# S7CAS-PLEIADES-CARTE-MERE_P20_USB.net
KiCad netlist of a schematic drawn in Altium Designer
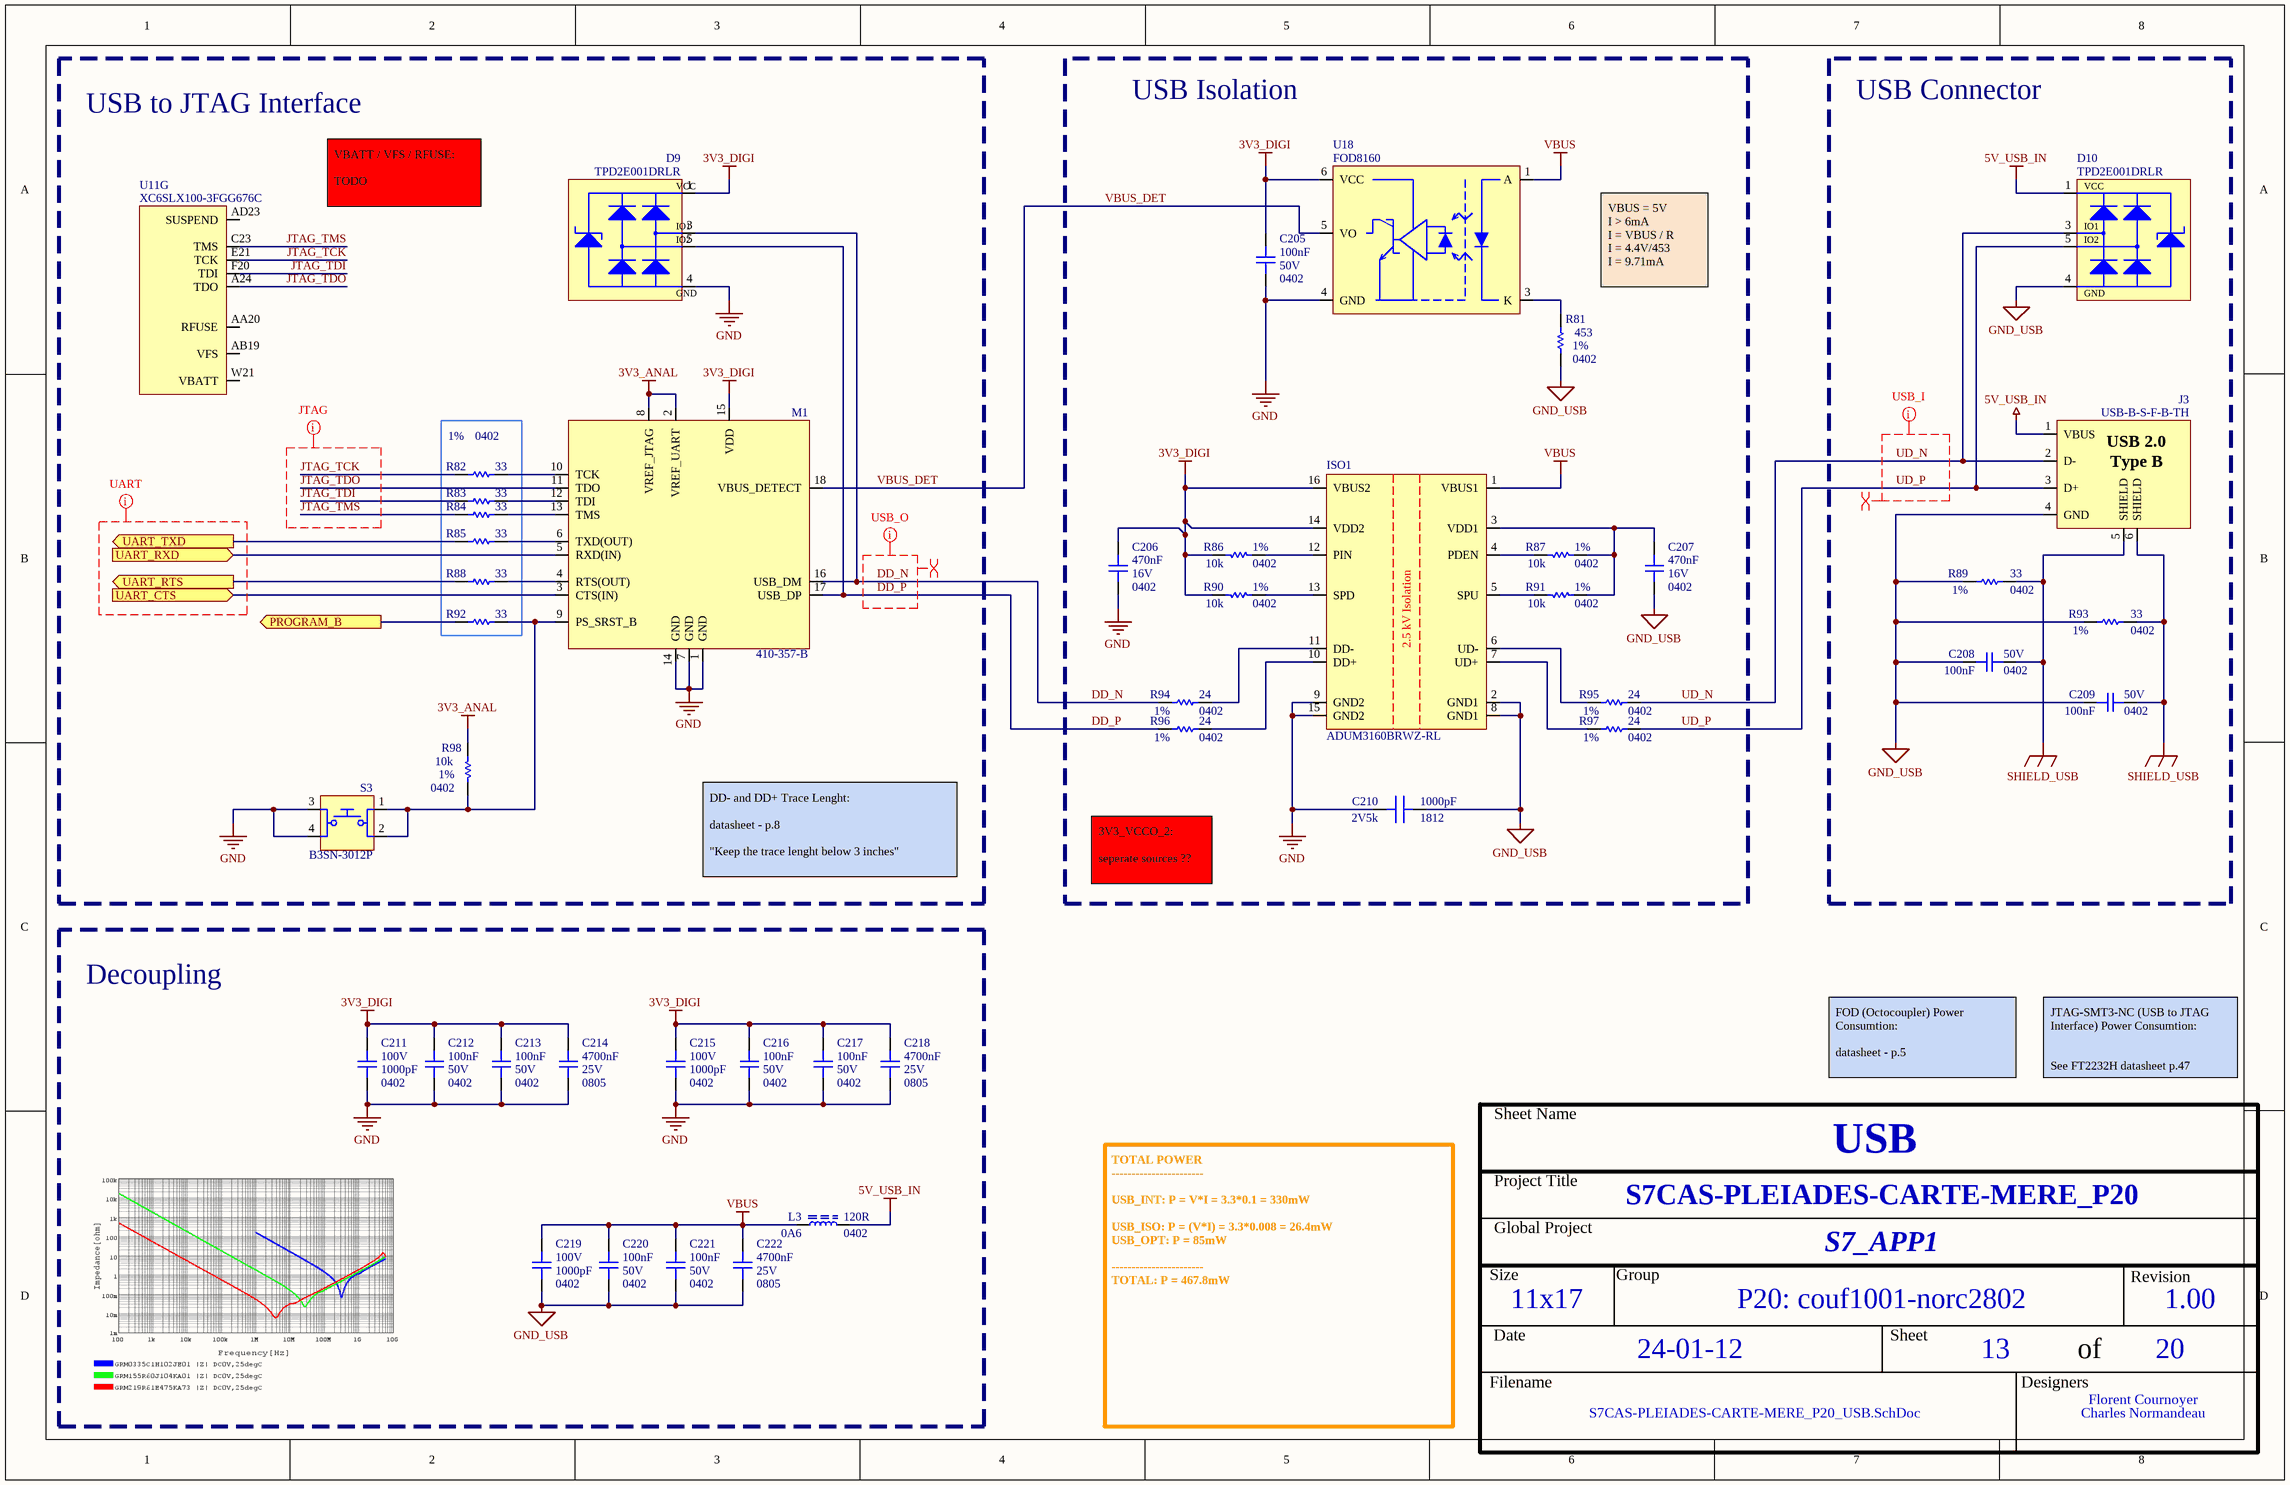
[diagram p0: S7CAS-PLEIADES-CARTE-MERE_P20_USB.SchDoc]

(export (version "E")
  (design (tool "Eeschema 10.0.6"))
  (components
    (comp (ref "C205")
      (value "100nF")
      (footprint "CAP_0402")
      (description "CAP - 0402")
      (fields
        (field (name "MFG PART NUMBER") "GRM155R61H104KE14")
        (field (name "VOLTAGE") "50V")
        (field (name "PACKAGE") "0402")
        (field (name "CREATEDBY") "Jonathan Bouchard")
      )
      (libsource (lib "S7CAS_LIB2023") (part "CAP - 0402"))
    )
    (comp (ref "C206")
      (value "470nF")
      (footprint "CAP_0402")
      (description "CAP - 0402")
      (fields
        (field (name "MFG PART NUMBER") "GXT155R61C474KE01")
        (field (name "VOLTAGE") "16V")
        (field (name "PACKAGE") "0402")
        (field (name "CREATEDBY") "Jonathan Bouchard")
      )
      (libsource (lib "S7CAS_LIB2023") (part "CAP - 0402"))
    )
    (comp (ref "C207")
      (value "470nF")
      (footprint "CAP_0402")
      (description "CAP - 0402")
      (fields
        (field (name "MFG PART NUMBER") "GXT155R61C474KE01")
        (field (name "VOLTAGE") "16V")
        (field (name "PACKAGE") "0402")
        (field (name "CREATEDBY") "Jonathan Bouchard")
      )
      (libsource (lib "S7CAS_LIB2023") (part "CAP - 0402"))
    )
    (comp (ref "C208")
      (value "100nF")
      (footprint "CAP_0402")
      (description "CAP - 0402")
      (fields
        (field (name "MFG PART NUMBER") "GRM155R61H104KE14")
        (field (name "VOLTAGE") "50V")
        (field (name "PACKAGE") "0402")
        (field (name "CREATEDBY") "Jonathan Bouchard")
      )
      (libsource (lib "S7CAS_LIB2023") (part "CAP - 0402"))
    )
    (comp (ref "C209")
      (value "100nF")
      (footprint "CAP_0402")
      (description "CAP - 0402")
      (fields
        (field (name "MFG PART NUMBER") "GRM155R61H104KE14")
        (field (name "VOLTAGE") "50V")
        (field (name "PACKAGE") "0402")
        (field (name "CREATEDBY") "Jonathan Bouchard")
      )
      (libsource (lib "S7CAS_LIB2023") (part "CAP - 0402"))
    )
    (comp (ref "C210")
      (value "1000pF")
      (footprint "CAP_CER_1812")
      (description "CAP - CER 1000PF 2.5KV X7R - 1812")
      (fields
        (field (name "TOLERANCE") "10%")
        (field (name "PACKAGE") "1812")
        (field (name "VOLTAGE RATING") "2V5k")
        (field (name "Comment") "1812WC102KAT1A")
      )
      (libsource (lib "LIB_TEMP_P20_FLORENT_COURNOYER_SCH") (part "CAP_CER_1812WC102KAT1A"))
    )
    (comp (ref "C211")
      (value "1000pF")
      (footprint "CAP_0402")
      (description "CAP - 0402")
      (fields
        (field (name "MFG PART NUMBER") "GRM155R72A102KA01")
        (field (name "VOLTAGE") "100V")
        (field (name "PACKAGE") "0402")
        (field (name "CREATEDBY") "Jonathan Bouchard")
      )
      (libsource (lib "S7CAS_LIB2023") (part "CAP - 0402"))
    )
    (comp (ref "C212")
      (value "100nF")
      (footprint "CAP_0402")
      (description "CAP - 0402")
      (fields
        (field (name "MFG PART NUMBER") "GRM155R61H104KE14")
        (field (name "VOLTAGE") "50V")
        (field (name "PACKAGE") "0402")
        (field (name "CREATEDBY") "Jonathan Bouchard")
      )
      (libsource (lib "S7CAS_LIB2023") (part "CAP - 0402"))
    )
    (comp (ref "C213")
      (value "100nF")
      (footprint "CAP_0402")
      (description "CAP - 0402")
      (fields
        (field (name "MFG PART NUMBER") "GRM155R61H104KE14")
        (field (name "VOLTAGE") "50V")
        (field (name "PACKAGE") "0402")
        (field (name "CREATEDBY") "Jonathan Bouchard")
      )
      (libsource (lib "S7CAS_LIB2023") (part "CAP - 0402"))
    )
    (comp (ref "C214")
      (value "4700nF")
      (footprint "CAP_0805")
      (description "CAP - 0805")
      (fields
        (field (name "MFG PART NUMBER") "GRM219R61E475KA73")
        (field (name "VOLTAGE") "25V")
        (field (name "PACKAGE") "0805")
        (field (name "CREATEDBY") "Jonathan Bouchard")
      )
      (libsource (lib "S7CAS_LIB2023") (part "CAP - 0805"))
    )
    (comp (ref "C215")
      (value "1000pF")
      (footprint "CAP_0402")
      (description "CAP - 0402")
      (fields
        (field (name "MFG PART NUMBER") "GRM155R72A102KA01")
        (field (name "VOLTAGE") "100V")
        (field (name "PACKAGE") "0402")
        (field (name "CREATEDBY") "Jonathan Bouchard")
      )
      (libsource (lib "S7CAS_LIB2023") (part "CAP - 0402"))
    )
    (comp (ref "C216")
      (value "100nF")
      (footprint "CAP_0402")
      (description "CAP - 0402")
      (fields
        (field (name "MFG PART NUMBER") "GRM155R61H104KE14")
        (field (name "VOLTAGE") "50V")
        (field (name "PACKAGE") "0402")
        (field (name "CREATEDBY") "Jonathan Bouchard")
      )
      (libsource (lib "S7CAS_LIB2023") (part "CAP - 0402"))
    )
    (comp (ref "C217")
      (value "100nF")
      (footprint "CAP_0402")
      (description "CAP - 0402")
      (fields
        (field (name "MFG PART NUMBER") "GRM155R61H104KE14")
        (field (name "VOLTAGE") "50V")
        (field (name "PACKAGE") "0402")
        (field (name "CREATEDBY") "Jonathan Bouchard")
      )
      (libsource (lib "S7CAS_LIB2023") (part "CAP - 0402"))
    )
    (comp (ref "C218")
      (value "4700nF")
      (footprint "CAP_0805")
      (description "CAP - 0805")
      (fields
        (field (name "MFG PART NUMBER") "GRM219R61E475KA73")
        (field (name "VOLTAGE") "25V")
        (field (name "PACKAGE") "0805")
        (field (name "CREATEDBY") "Jonathan Bouchard")
      )
      (libsource (lib "S7CAS_LIB2023") (part "CAP - 0805"))
    )
    (comp (ref "C219")
      (value "1000pF")
      (footprint "CAP_0402")
      (description "CAP - 0402")
      (fields
        (field (name "MFG PART NUMBER") "GRM155R72A102KA01")
        (field (name "VOLTAGE") "100V")
        (field (name "PACKAGE") "0402")
        (field (name "CREATEDBY") "Jonathan Bouchard")
      )
      (libsource (lib "S7CAS_LIB2023") (part "CAP - 0402"))
    )
    (comp (ref "C220")
      (value "100nF")
      (footprint "CAP_0402")
      (description "CAP - 0402")
      (fields
        (field (name "MFG PART NUMBER") "GRM155R61H104KE14")
        (field (name "VOLTAGE") "50V")
        (field (name "PACKAGE") "0402")
        (field (name "CREATEDBY") "Jonathan Bouchard")
      )
      (libsource (lib "S7CAS_LIB2023") (part "CAP - 0402"))
    )
    (comp (ref "C221")
      (value "100nF")
      (footprint "CAP_0402")
      (description "CAP - 0402")
      (fields
        (field (name "MFG PART NUMBER") "GRM155R61H104KE14")
        (field (name "VOLTAGE") "50V")
        (field (name "PACKAGE") "0402")
        (field (name "CREATEDBY") "Jonathan Bouchard")
      )
      (libsource (lib "S7CAS_LIB2023") (part "CAP - 0402"))
    )
    (comp (ref "C222")
      (value "4700nF")
      (footprint "CAP_0805")
      (description "CAP - 0805")
      (fields
        (field (name "MFG PART NUMBER") "GRM219R61E475KA73")
        (field (name "VOLTAGE") "25V")
        (field (name "PACKAGE") "0805")
        (field (name "CREATEDBY") "Jonathan Bouchard")
      )
      (libsource (lib "S7CAS_LIB2023") (part "CAP - 0805"))
    )
    (comp (ref "D9")
      (value "TPD2E001DRLR")
      (footprint "TVS_USB_TPD2E001DRLR")
      (description "TVS - USB TVS DIODE 5.5V - SOT-553")
      (fields
        (field (name "CREATEDBY/DATE") "Jonathan Bouchard 2018-07-10")
        (field (name "VERIFIEDBY") "Arnaud Samson 16-07-18")
      )
      (libsource (lib "") (part "TVS_USB_TPD2E001DRLR_1"))
    )
    (comp (ref "D10")
      (value "TPD2E001DRLR")
      (footprint "TVS_USB_TPD2E001DRLR")
      (description "TVS - USB TVS DIODE 5.5V - SOT-553")
      (fields
        (field (name "CREATEDBY/DATE") "Jonathan Bouchard 2018-07-10")
        (field (name "VERIFIEDBY") "Arnaud Samson 16-07-18")
      )
      (libsource (lib "S7CAS_LIB2023") (part "TVS_USB_TPD2E001DRLR"))
    )
    (comp (ref "ISO1")
      (value "ADUM3160BRWZ-RL")
      (footprint "ISO_ADUM3160BRWZ-RL")
      (description "ISO - DGTL ISO 2.5KV 2CH USB - 16SOIC")
      (fields
        (field (name "CREATEDBY/DATE") "Tommy Rossignol 2018-11-16")
        (field (name "VERIFIEDBY") "Caroline Paulin - 13 février 2019")
      )
      (libsource (lib "S7CAS_LIB2023") (part "ISO_ADUM3160BRWZ-RL"))
    )
    (comp (ref "J3")
      (value "USB-B-S-F-B-TH")
      (footprint "CON_USB_USB-B-S-F-B-TH")
      (description "CON - USB B RECPT TH R/A - 4-TH")
      (fields
        (field (name "MFG PART NUMBER") "CON_USB_USB-B-S-F-B-TH")
        (field (name "CREATEDBY/DATE") "Jonathan Bouchard 2020-03-24")
        (field (name "VERIFIEDBY") "C.Paulin - 22/04/2020")
      )
      (libsource (lib "S7CAS_LIB2023") (part "CON_USB_USB-B-S-F-B-TH"))
    )
    (comp (ref "L3")
      (value "120R")
      (footprint "FER_0402")
      (description "FER - 0402")
      (fields
        (field (name "MFG PART NUMBER") "BLM15BX121SN1")
        (field (name "CURRENT") "0A6")
        (field (name "PACKAGE") "0402")
        (field (name "CREATEDBY") "Jonathan Bouchard")
      )
      (libsource (lib "S7CAS_LIB2023") (part "FER - 0402"))
    )
    (comp (ref "M1")
      (value "410-357-B")
      (footprint "MOD_JTAG_410-357-B")
      (description "MOD - JTAG-SMT3-NC Programming Module For Xilinx FPGA - 18-SMT")
      (fields
        (field (name "CREATEDBY/DATE") "Tommy Rossignol 2018-11-23")
        (field (name "VERIFIEDBY") "Nicolas V. (2019-01-28)")
      )
      (libsource (lib "S7CAS_LIB2023") (part "MOD_JTAG_410-357-B"))
    )
    (comp (ref "R81")
      (value "453")
      (footprint "RES_0402")
      (description "RES - 0402")
      (fields
        (field (name "VOLTAGE") "50V")
        (field (name "MFG PART NUMBER") "RGC1/16SC6980FTH")
        (field (name "PACKAGE") "0402")
        (field (name "PRECISION") "1%")
        (field (name "CREATEDBY") "Jonathan Bouchard")
      )
      (libsource (lib "S7CAS_LIB2023") (part "RES - 0402"))
    )
    (comp (ref "R82")
      (value "33")
      (footprint "RES_0402")
      (description "RES - 0402")
      (fields
        (field (name "VOLTAGE") "50V")
        (field (name "POWER") "1/16W")
        (field (name "PACKAGE") "0402")
        (field (name "PRECISION") "1%")
        (field (name "CREATEDBY") "Jonathan Bouchard")
      )
      (libsource (lib "S7CAS_LIB2023") (part "RES - 0402"))
    )
    (comp (ref "R83")
      (value "33")
      (footprint "RES_0402")
      (description "RES - 0402")
      (fields
        (field (name "VOLTAGE") "50V")
        (field (name "POWER") "1/16W")
        (field (name "CREATEDBY") "Jonathan Bouchard")
      )
      (libsource (lib "S7CAS_LIB2023") (part "RES - 0402"))
    )
    (comp (ref "R84")
      (value "33")
      (footprint "RES_0402")
      (description "RES - 0402")
      (fields
        (field (name "VOLTAGE") "50V")
        (field (name "POWER") "1/16W")
        (field (name "CREATEDBY") "Jonathan Bouchard")
      )
      (libsource (lib "S7CAS_LIB2023") (part "RES - 0402"))
    )
    (comp (ref "R85")
      (value "33")
      (footprint "RES_0402")
      (description "RES - 0402")
      (fields
        (field (name "VOLTAGE") "50V")
        (field (name "POWER") "1/16W")
        (field (name "CREATEDBY") "Jonathan Bouchard")
      )
      (libsource (lib "S7CAS_LIB2023") (part "RES - 0402"))
    )
    (comp (ref "R86")
      (value "10k")
      (footprint "RES_0402")
      (description "RES - 0402")
      (fields
        (field (name "VOLTAGE") "50V")
        (field (name "MFG PART NUMBER") "MCS04020C1002FE000")
        (field (name "PACKAGE") "0402")
        (field (name "PRECISION") "1%")
        (field (name "CREATEDBY") "Jonathan Bouchard")
      )
      (libsource (lib "S7CAS_LIB2023") (part "RES - 0402"))
    )
    (comp (ref "R87")
      (value "10k")
      (footprint "RES_0402")
      (description "RES - 0402")
      (fields
        (field (name "VOLTAGE") "50V")
        (field (name "MFG PART NUMBER") "MCS04020C1002FE000")
        (field (name "PACKAGE") "0402")
        (field (name "PRECISION") "1%")
        (field (name "CREATEDBY") "Jonathan Bouchard")
      )
      (libsource (lib "S7CAS_LIB2023") (part "RES - 0402"))
    )
    (comp (ref "R88")
      (value "33")
      (footprint "RES_0402")
      (description "RES - 0402")
      (fields
        (field (name "VOLTAGE") "50V")
        (field (name "POWER") "1/16W")
        (field (name "CREATEDBY") "Jonathan Bouchard")
      )
      (libsource (lib "S7CAS_LIB2023") (part "RES - 0402"))
    )
    (comp (ref "R89")
      (value "33")
      (footprint "RES_0402")
      (description "RES - 0402")
      (fields
        (field (name "VOLTAGE") "50V")
        (field (name "POWER") "1/16W")
        (field (name "PACKAGE") "0402")
        (field (name "PRECISION") "1%")
        (field (name "CREATEDBY") "Jonathan Bouchard")
      )
      (libsource (lib "S7CAS_LIB2023") (part "RES - 0402"))
    )
    (comp (ref "R90")
      (value "10k")
      (footprint "RES_0402")
      (description "RES - 0402")
      (fields
        (field (name "VOLTAGE") "50V")
        (field (name "MFG PART NUMBER") "MCS04020C1002FE000")
        (field (name "PACKAGE") "0402")
        (field (name "PRECISION") "1%")
        (field (name "CREATEDBY") "Jonathan Bouchard")
      )
      (libsource (lib "S7CAS_LIB2023") (part "RES - 0402"))
    )
    (comp (ref "R91")
      (value "10k")
      (footprint "RES_0402")
      (description "RES - 0402")
      (fields
        (field (name "VOLTAGE") "50V")
        (field (name "MFG PART NUMBER") "MCS04020C1002FE000")
        (field (name "PACKAGE") "0402")
        (field (name "PRECISION") "1%")
        (field (name "CREATEDBY") "Jonathan Bouchard")
      )
      (libsource (lib "S7CAS_LIB2023") (part "RES - 0402"))
    )
    (comp (ref "R92")
      (value "33")
      (footprint "RES_0402")
      (description "RES - 0402")
      (fields
        (field (name "VOLTAGE") "50V")
        (field (name "POWER") "1/16W")
        (field (name "CREATEDBY") "Jonathan Bouchard")
      )
      (libsource (lib "S7CAS_LIB2023") (part "RES - 0402"))
    )
    (comp (ref "R93")
      (value "33")
      (footprint "RES_0402")
      (description "RES - 0402")
      (fields
        (field (name "VOLTAGE") "50V")
        (field (name "POWER") "1/16W")
        (field (name "PACKAGE") "0402")
        (field (name "PRECISION") "1%")
        (field (name "CREATEDBY") "Jonathan Bouchard")
      )
      (libsource (lib "S7CAS_LIB2023") (part "RES - 0402"))
    )
    (comp (ref "R94")
      (value "24")
      (footprint "RES_0402")
      (description "RES - 0402")
      (fields
        (field (name "VOLTAGE") "50V")
        (field (name "MFG PART NUMBER") "MCS04020C2409FE000")
        (field (name "PACKAGE") "0402")
        (field (name "PRECISION") "1%")
        (field (name "CREATEDBY") "Jonathan Bouchard")
      )
      (libsource (lib "S7CAS_LIB2023") (part "RES - 0402"))
    )
    (comp (ref "R95")
      (value "24")
      (footprint "RES_0402")
      (description "RES - 0402")
      (fields
        (field (name "VOLTAGE") "50V")
        (field (name "MFG PART NUMBER") "MCS04020C2409FE000")
        (field (name "PACKAGE") "0402")
        (field (name "PRECISION") "1%")
        (field (name "CREATEDBY") "Jonathan Bouchard")
      )
      (libsource (lib "S7CAS_LIB2023") (part "RES - 0402"))
    )
    (comp (ref "R96")
      (value "24")
      (footprint "RES_0402")
      (description "RES - 0402")
      (fields
        (field (name "VOLTAGE") "50V")
        (field (name "MFG PART NUMBER") "MCS04020C2409FE000")
        (field (name "PACKAGE") "0402")
        (field (name "PRECISION") "1%")
        (field (name "CREATEDBY") "Jonathan Bouchard")
      )
      (libsource (lib "S7CAS_LIB2023") (part "RES - 0402"))
    )
    (comp (ref "R97")
      (value "24")
      (footprint "RES_0402")
      (description "RES - 0402")
      (fields
        (field (name "VOLTAGE") "50V")
        (field (name "MFG PART NUMBER") "MCS04020C2409FE000")
        (field (name "PACKAGE") "0402")
        (field (name "PRECISION") "1%")
        (field (name "CREATEDBY") "Jonathan Bouchard")
      )
      (libsource (lib "S7CAS_LIB2023") (part "RES - 0402"))
    )
    (comp (ref "R98")
      (value "10k")
      (footprint "RES_0402")
      (description "RES - 0402")
      (fields
        (field (name "VOLTAGE") "50V")
        (field (name "MFG PART NUMBER") "MCS04020C1002FE000")
        (field (name "PACKAGE") "0402")
        (field (name "PRECISION") "1%")
        (field (name "CREATEDBY") "Jonathan Bouchard")
      )
      (libsource (lib "S7CAS_LIB2023") (part "RES - 0402"))
    )
    (comp (ref "S3")
      (value "B3SN-3012P")
      (footprint "SWI_TACT_B3SN-3012P")
      (description "SWI - SWITCH TACTILE SPST-NO 0.05A 24V -SMD")
      (fields
        (field (name "CREATEDBY/DATE") "Olivier Bernard / 5/12/2017")
        (field (name "VERIFIEDBY") "Caroline Paulin / 11 juillet 2018")
      )
      (libsource (lib "S7CAS_LIB2023") (part "SWI_TACT_B3SN-3012P_1"))
    )
    (comp (ref "U11")
      (value "XC6SLX100-3FGG676C")
      (footprint "FPGA_XILINX_FGG676")
      (description "FPGA - XILINX SPARTAN 6 480 I/O - BGA-676")
      (fields
        (field (name "VOLTAGE") "1.14 V ~ 1.26 V")
        (field (name "MFG") "Xilinx")
        (field (name "CREATEDBY") "Jonathan Bouchard")
      )
      (libsource (lib "S7CAS_LIB2023") (part "FPGA_XC6SLX100-3FGG676C"))
    )
    (comp (ref "U18")
      (value "FOD8160")
      (footprint "FOD8160")
      (description "XXX - Description - Package")
      (libsource (lib "LIB_TEMP_P20_FLORENT_COURNOYER_SCH") (part "OCTOCOUPLER_FOD8160"))
    )
  )
  (nets
    (net (code "1") (name "/DD_N") (class "Default")
      (node (ref "D9") (pin "3") (pinfunction "IO1_3") (pintype "passive"))
      (node (ref "M1") (pin "16") (pinfunction "USB_DM_16") (pintype "passive"))
      (node (ref "R94") (pin "2") (pinfunction "2_2") (pintype "passive"))
    )
    (net (code "2") (name "/DD_P") (class "Default")
      (node (ref "D9") (pin "5") (pinfunction "IO2_5") (pintype "passive"))
      (node (ref "M1") (pin "17") (pinfunction "USB_DP_17") (pintype "passive"))
      (node (ref "R96") (pin "2") (pinfunction "2_2") (pintype "passive"))
    )
    (net (code "3") (name "/JTAG_TCK") (class "Default")
      (node (ref "R82") (pin "2") (pinfunction "2_2") (pintype "passive"))
      (node (ref "U11") (pin "E21") (pinfunction "TCK_E21") (pintype "passive"))
    )
    (net (code "4") (name "/JTAG_TDI") (class "Default")
      (node (ref "R83") (pin "2") (pinfunction "2_2") (pintype "passive"))
      (node (ref "U11") (pin "F20") (pinfunction "TDI_F20") (pintype "passive"))
    )
    (net (code "5") (name "/JTAG_TDO") (class "Default")
      (node (ref "M1") (pin "11") (pinfunction "TDO_11") (pintype "passive"))
      (node (ref "U11") (pin "A24") (pinfunction "TDO_A24") (pintype "passive"))
    )
    (net (code "6") (name "/JTAG_TMS") (class "Default")
      (node (ref "R84") (pin "2") (pinfunction "2_2") (pintype "passive"))
      (node (ref "U11") (pin "C23") (pinfunction "TMS_C23") (pintype "passive"))
    )
    (net (code "7") (name "/PROGRAM_B") (class "Default")
      (node (ref "R92") (pin "2") (pinfunction "2_2") (pintype "passive"))
    )
    (net (code "8") (name "/UART_CTS") (class "Default")
      (node (ref "M1") (pin "3") (pinfunction "CTS(IN)_3") (pintype "passive"))
    )
    (net (code "9") (name "/UART_RTS") (class "Default")
      (node (ref "R88") (pin "2") (pinfunction "2_2") (pintype "passive"))
    )
    (net (code "10") (name "/UART_RXD") (class "Default")
      (node (ref "M1") (pin "5") (pinfunction "RXD(IN)_5") (pintype "passive"))
    )
    (net (code "11") (name "/UART_TXD") (class "Default")
      (node (ref "R85") (pin "2") (pinfunction "2_2") (pintype "passive"))
    )
    (net (code "12") (name "/UD_N") (class "Default")
      (node (ref "D10") (pin "3") (pinfunction "IO1_3") (pintype "passive"))
      (node (ref "J3") (pin "2") (pinfunction "D-_2") (pintype "passive"))
      (node (ref "R95") (pin "1") (pinfunction "1_1") (pintype "passive"))
    )
    (net (code "13") (name "/UD_P") (class "Default")
      (node (ref "D10") (pin "5") (pinfunction "IO2_5") (pintype "passive"))
      (node (ref "J3") (pin "3") (pinfunction "D+_3") (pintype "passive"))
      (node (ref "R97") (pin "1") (pinfunction "1_1") (pintype "passive"))
    )
    (net (code "14") (name "/VBUS_DET") (class "Default")
      (node (ref "M1") (pin "18") (pinfunction "VBUS_DETECT_18") (pintype "passive"))
      (node (ref "U18") (pin "5") (pinfunction "VO_5") (pintype "passive"))
    )
    (net (code "15") (name "3V3_ANAL") (class "Default")
      (node (ref "M1") (pin "2") (pinfunction "VREF_UART_2") (pintype "passive"))
      (node (ref "M1") (pin "8") (pinfunction "VREF_JTAG_8") (pintype "passive"))
      (node (ref "R98") (pin "2") (pinfunction "2_2") (pintype "passive"))
    )
    (net (code "16") (name "3V3_DIGI") (class "Default")
      (node (ref "C205") (pin "2") (pinfunction "2_2") (pintype "passive"))
      (node (ref "C206") (pin "2") (pinfunction "2_2") (pintype "passive"))
      (node (ref "C211") (pin "1") (pinfunction "1_1") (pintype "passive"))
      (node (ref "C212") (pin "2") (pinfunction "2_2") (pintype "passive"))
      (node (ref "C213") (pin "2") (pinfunction "2_2") (pintype "passive"))
      (node (ref "C214") (pin "2") (pinfunction "2_2") (pintype "passive"))
      (node (ref "C215") (pin "1") (pinfunction "1_1") (pintype "passive"))
      (node (ref "C216") (pin "2") (pinfunction "2_2") (pintype "passive"))
      (node (ref "C217") (pin "2") (pinfunction "2_2") (pintype "passive"))
      (node (ref "C218") (pin "2") (pinfunction "2_2") (pintype "passive"))
      (node (ref "D9") (pin "1") (pinfunction "VCC_1") (pintype "passive"))
      (node (ref "ISO1") (pin "14") (pinfunction "VDD2_14") (pintype "passive"))
      (node (ref "ISO1") (pin "16") (pinfunction "VBUS2_16") (pintype "passive"))
      (node (ref "M1") (pin "15") (pinfunction "VDD_15") (pintype "passive"))
      (node (ref "R86") (pin "2") (pinfunction "2_2") (pintype "passive"))
      (node (ref "R90") (pin "2") (pinfunction "2_2") (pintype "passive"))
      (node (ref "U18") (pin "6") (pinfunction "VCC_6") (pintype "passive"))
    )
    (net (code "17") (name "5V_USB_IN") (class "Default")
      (node (ref "D10") (pin "1") (pinfunction "VCC_1") (pintype "passive"))
      (node (ref "J3") (pin "1") (pinfunction "VBUS_1") (pintype "passive"))
      (node (ref "L3") (pin "1") (pinfunction "1_1") (pintype "passive"))
    )
    (net (code "18") (name "GND") (class "Default")
      (node (ref "C205") (pin "1") (pinfunction "1_1") (pintype "passive"))
      (node (ref "C206") (pin "1") (pinfunction "1_1") (pintype "passive"))
      (node (ref "C210") (pin "2") (pinfunction "2_2") (pintype "passive"))
      (node (ref "C211") (pin "2") (pinfunction "2_2") (pintype "passive"))
      (node (ref "C212") (pin "1") (pinfunction "1_1") (pintype "passive"))
      (node (ref "C213") (pin "1") (pinfunction "1_1") (pintype "passive"))
      (node (ref "C214") (pin "1") (pinfunction "1_1") (pintype "passive"))
      (node (ref "C215") (pin "2") (pinfunction "2_2") (pintype "passive"))
      (node (ref "C216") (pin "1") (pinfunction "1_1") (pintype "passive"))
      (node (ref "C217") (pin "1") (pinfunction "1_1") (pintype "passive"))
      (node (ref "C218") (pin "1") (pinfunction "1_1") (pintype "passive"))
      (node (ref "D9") (pin "4") (pinfunction "GND_4") (pintype "passive"))
      (node (ref "ISO1") (pin "15") (pinfunction "GND2_15") (pintype "passive"))
      (node (ref "ISO1") (pin "9") (pinfunction "GND2_9") (pintype "passive"))
      (node (ref "M1") (pin "1") (pinfunction "GND_1") (pintype "passive"))
      (node (ref "M1") (pin "14") (pinfunction "GND_14") (pintype "passive"))
      (node (ref "M1") (pin "7") (pinfunction "GND_7") (pintype "passive"))
      (node (ref "S3") (pin "3") (pinfunction "3_3") (pintype "passive"))
      (node (ref "S3") (pin "4") (pinfunction "4_4") (pintype "passive"))
      (node (ref "U18") (pin "4") (pinfunction "GND_4") (pintype "passive"))
    )
    (net (code "19") (name "GND_USB") (class "Default")
      (node (ref "C207") (pin "1") (pinfunction "1_1") (pintype "passive"))
      (node (ref "C208") (pin "2") (pinfunction "2_2") (pintype "passive"))
      (node (ref "C209") (pin "2") (pinfunction "2_2") (pintype "passive"))
      (node (ref "C210") (pin "1") (pinfunction "1_1") (pintype "passive"))
      (node (ref "C219") (pin "2") (pinfunction "2_2") (pintype "passive"))
      (node (ref "C220") (pin "1") (pinfunction "1_1") (pintype "passive"))
      (node (ref "C221") (pin "1") (pinfunction "1_1") (pintype "passive"))
      (node (ref "C222") (pin "1") (pinfunction "1_1") (pintype "passive"))
      (node (ref "D10") (pin "4") (pinfunction "GND_4") (pintype "passive"))
      (node (ref "ISO1") (pin "2") (pinfunction "GND1_2") (pintype "passive"))
      (node (ref "ISO1") (pin "8") (pinfunction "GND1_8") (pintype "passive"))
      (node (ref "J3") (pin "4") (pinfunction "GND_4") (pintype "passive"))
      (node (ref "R81") (pin "1") (pinfunction "1_1") (pintype "passive"))
      (node (ref "R89") (pin "2") (pinfunction "2_2") (pintype "passive"))
      (node (ref "R93") (pin "2") (pinfunction "2_2") (pintype "passive"))
    )
    (net (code "20") (name "Net-(ISO1-DD+)") (class "Default")
      (node (ref "ISO1") (pin "10") (pinfunction "DD+_10") (pintype "passive"))
      (node (ref "R96") (pin "1") (pinfunction "1_1") (pintype "passive"))
    )
    (net (code "21") (name "Net-(ISO1-DD-)") (class "Default")
      (node (ref "ISO1") (pin "11") (pinfunction "DD-_11") (pintype "passive"))
      (node (ref "R94") (pin "1") (pinfunction "1_1") (pintype "passive"))
    )
    (net (code "22") (name "Net-(ISO1-PDEN)") (class "Default")
      (node (ref "ISO1") (pin "4") (pinfunction "PDEN_4") (pintype "passive"))
      (node (ref "R87") (pin "2") (pinfunction "2_2") (pintype "passive"))
    )
    (net (code "23") (name "Net-(ISO1-PIN)") (class "Default")
      (node (ref "ISO1") (pin "12") (pinfunction "PIN_12") (pintype "passive"))
      (node (ref "R86") (pin "1") (pinfunction "1_1") (pintype "passive"))
    )
    (net (code "24") (name "Net-(ISO1-SPD)") (class "Default")
      (node (ref "ISO1") (pin "13") (pinfunction "SPD_13") (pintype "passive"))
      (node (ref "R90") (pin "1") (pinfunction "1_1") (pintype "passive"))
    )
    (net (code "25") (name "Net-(ISO1-SPU)") (class "Default")
      (node (ref "ISO1") (pin "5") (pinfunction "SPU_5") (pintype "passive"))
      (node (ref "R91") (pin "2") (pinfunction "2_2") (pintype "passive"))
    )
    (net (code "26") (name "Net-(ISO1-UD+)") (class "Default")
      (node (ref "ISO1") (pin "7") (pinfunction "UD+_7") (pintype "passive"))
      (node (ref "R97") (pin "2") (pinfunction "2_2") (pintype "passive"))
    )
    (net (code "27") (name "Net-(ISO1-UD-)") (class "Default")
      (node (ref "ISO1") (pin "6") (pinfunction "UD-_6") (pintype "passive"))
      (node (ref "R95") (pin "2") (pinfunction "2_2") (pintype "passive"))
    )
    (net (code "28") (name "Net-(ISO1-VDD1)") (class "Default")
      (node (ref "C207") (pin "2") (pinfunction "2_2") (pintype "passive"))
      (node (ref "ISO1") (pin "3") (pinfunction "VDD1_3") (pintype "passive"))
      (node (ref "R87") (pin "1") (pinfunction "1_1") (pintype "passive"))
      (node (ref "R91") (pin "1") (pinfunction "1_1") (pintype "passive"))
    )
    (net (code "29") (name "Net-(M1-PS_SRST_B)") (class "Default")
      (node (ref "M1") (pin "9") (pinfunction "PS_SRST_B_9") (pintype "passive"))
      (node (ref "R92") (pin "1") (pinfunction "1_1") (pintype "passive"))
      (node (ref "R98") (pin "1") (pinfunction "1_1") (pintype "passive"))
      (node (ref "S3") (pin "1") (pinfunction "1_1") (pintype "passive"))
      (node (ref "S3") (pin "2") (pinfunction "2_2") (pintype "passive"))
    )
    (net (code "30") (name "Net-(M1-RTS(OUT))") (class "Default")
      (node (ref "M1") (pin "4") (pinfunction "RTS(OUT)_4") (pintype "passive"))
      (node (ref "R88") (pin "1") (pinfunction "1_1") (pintype "passive"))
    )
    (net (code "31") (name "Net-(M1-TCK)") (class "Default")
      (node (ref "M1") (pin "10") (pinfunction "TCK_10") (pintype "passive"))
      (node (ref "R82") (pin "1") (pinfunction "1_1") (pintype "passive"))
    )
    (net (code "32") (name "Net-(M1-TDI)") (class "Default")
      (node (ref "M1") (pin "12") (pinfunction "TDI_12") (pintype "passive"))
      (node (ref "R83") (pin "1") (pinfunction "1_1") (pintype "passive"))
    )
    (net (code "33") (name "Net-(M1-TMS)") (class "Default")
      (node (ref "M1") (pin "13") (pinfunction "TMS_13") (pintype "passive"))
      (node (ref "R84") (pin "1") (pinfunction "1_1") (pintype "passive"))
    )
    (net (code "34") (name "Net-(M1-TXD(OUT))") (class "Default")
      (node (ref "M1") (pin "6") (pinfunction "TXD(OUT)_6") (pintype "passive"))
      (node (ref "R85") (pin "1") (pinfunction "1_1") (pintype "passive"))
    )
    (net (code "35") (name "Net-(U18-K)") (class "Default")
      (node (ref "R81") (pin "2") (pinfunction "2_2") (pintype "passive"))
      (node (ref "U18") (pin "3") (pinfunction "K_3") (pintype "passive"))
    )
    (net (code "36") (name "SHIELD_USB") (class "Default")
      (node (ref "C208") (pin "1") (pinfunction "1_1") (pintype "passive"))
      (node (ref "C209") (pin "1") (pinfunction "1_1") (pintype "passive"))
      (node (ref "J3") (pin "5") (pinfunction "SHIELD_5") (pintype "passive"))
      (node (ref "J3") (pin "6") (pinfunction "SHIELD_6") (pintype "passive"))
      (node (ref "R89") (pin "1") (pinfunction "1_1") (pintype "passive"))
      (node (ref "R93") (pin "1") (pinfunction "1_1") (pintype "passive"))
    )
    (net (code "37") (name "VBUS") (class "Default")
      (node (ref "C219") (pin "1") (pinfunction "1_1") (pintype "passive"))
      (node (ref "C220") (pin "2") (pinfunction "2_2") (pintype "passive"))
      (node (ref "C221") (pin "2") (pinfunction "2_2") (pintype "passive"))
      (node (ref "C222") (pin "2") (pinfunction "2_2") (pintype "passive"))
      (node (ref "ISO1") (pin "1") (pinfunction "VBUS1_1") (pintype "passive"))
      (node (ref "L3") (pin "2") (pinfunction "2_2") (pintype "passive"))
      (node (ref "U18") (pin "1") (pinfunction "A_1") (pintype "passive"))
    )
    (net (code "38") (name "unconnected-(D9-NC-Pad2)") (class "Default")
      (node (ref "D9") (pin "2") (pinfunction "NC_2") (pintype "passive"))
    )
    (net (code "39") (name "unconnected-(D10-NC-Pad2)") (class "Default")
      (node (ref "D10") (pin "2") (pinfunction "NC_2") (pintype "passive"))
    )
    (net (code "40") (name "unconnected-(U11G-RFUSE-PadAA20)") (class "Default")
      (node (ref "U11") (pin "AA20") (pinfunction "RFUSE_AA20") (pintype "passive"))
    )
    (net (code "41") (name "unconnected-(U11G-SUSPEND-PadAD23)") (class "Default")
      (node (ref "U11") (pin "AD23") (pinfunction "SUSPEND_AD23") (pintype "passive"))
    )
    (net (code "42") (name "unconnected-(U11G-VBATT-PadW21)") (class "Default")
      (node (ref "U11") (pin "W21") (pinfunction "VBATT_W21") (pintype "passive"))
    )
    (net (code "43") (name "unconnected-(U11G-VFS-PadAB19)") (class "Default")
      (node (ref "U11") (pin "AB19") (pinfunction "VFS_AB19") (pintype "passive"))
    )
  )
)
